# openVTI-Shield-RevC.net
KiCad netlist of a schematic drawn in EAGLE
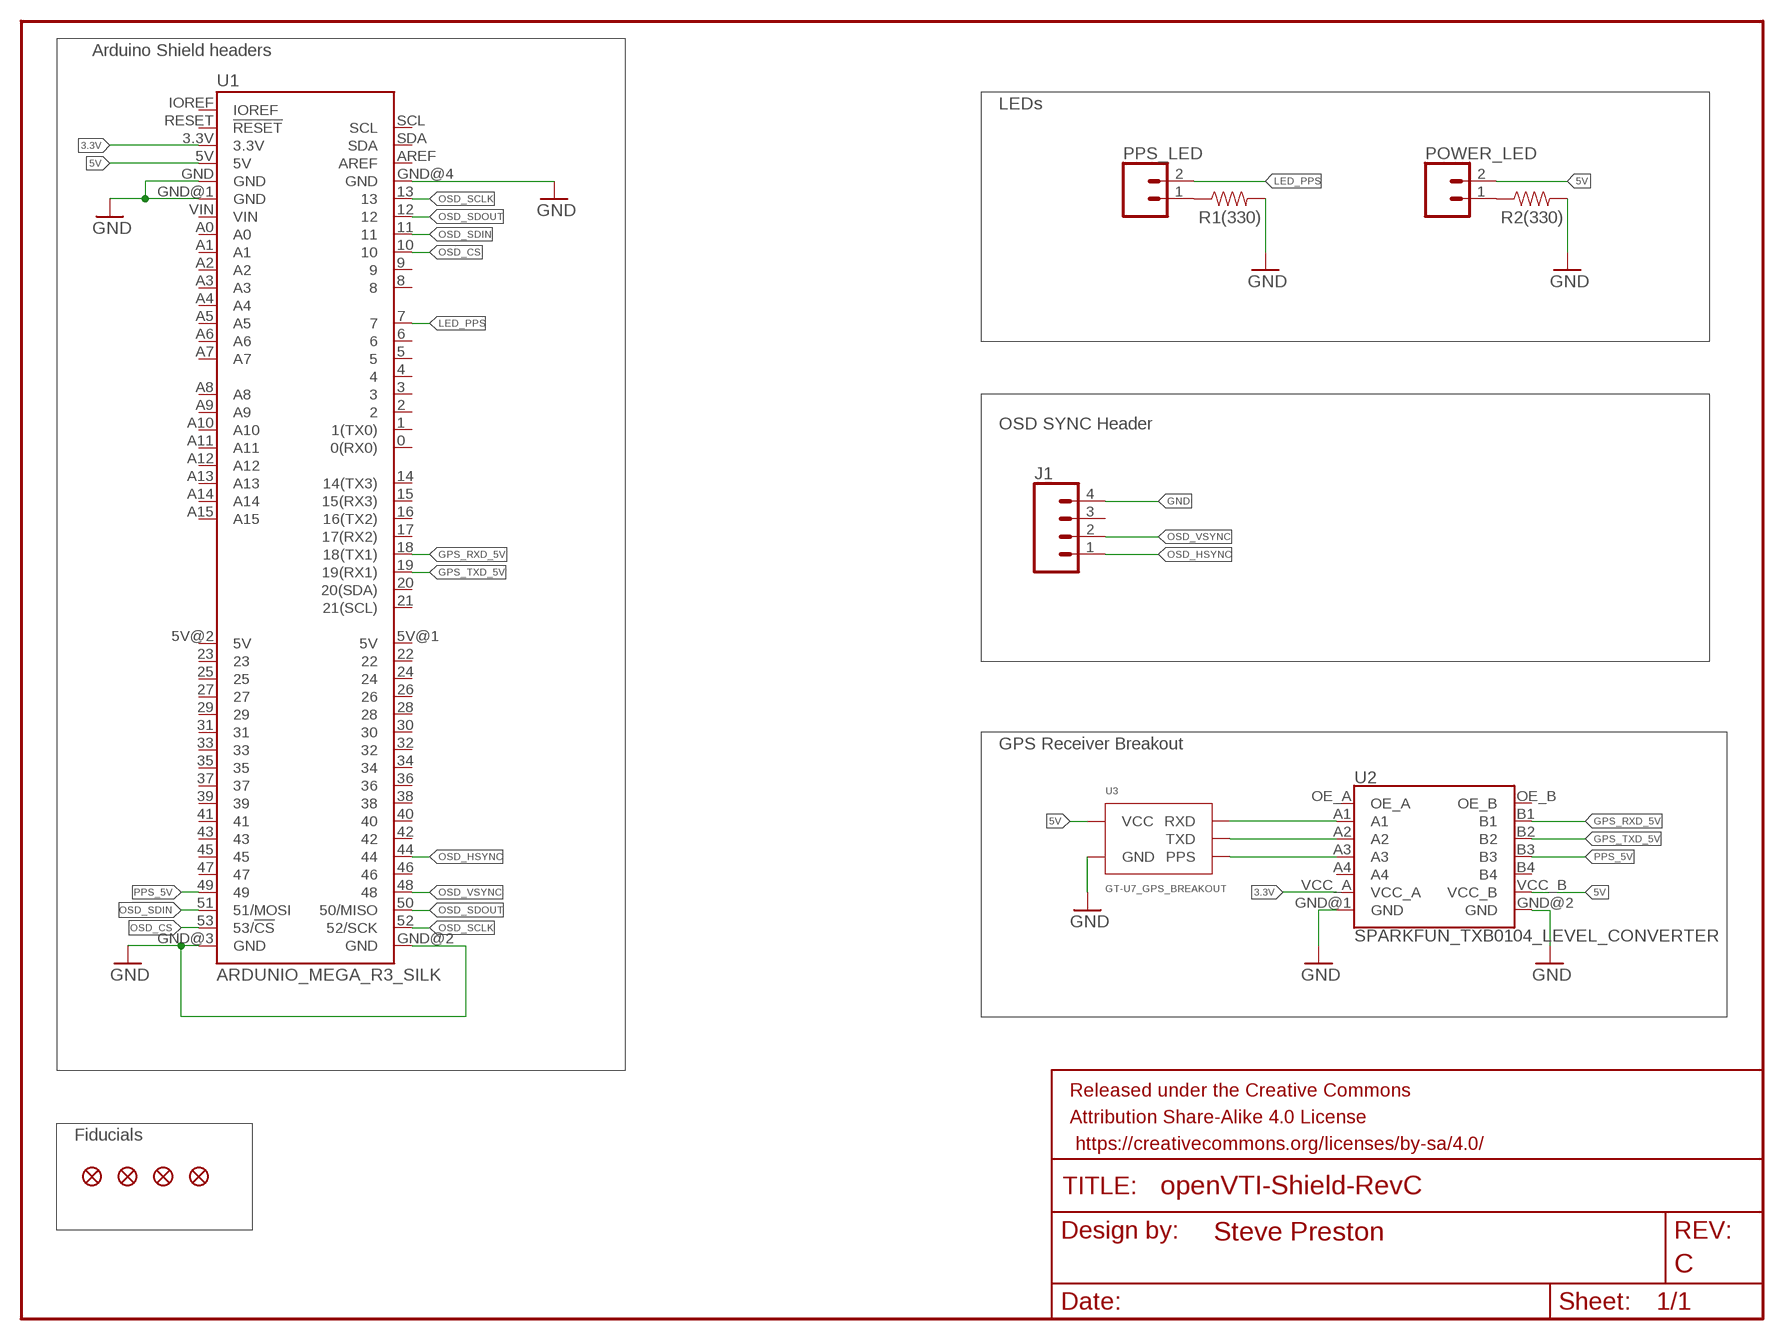
[diagram p0: schematic, sheet 1]

(export (version "E")
  (design (tool "Eeschema 10.0.6"))
  (components
    (comp (ref "FD1")
      (value "FIDUCIALUFIDUCIAL")
      (footprint "eagle-import:FIDUCIAL-MICRO")
      (libsource (lib "eagle-import") (part "FIDUCIALUFIDUCIAL"))
    )
    (comp (ref "FD2")
      (value "FIDUCIALUFIDUCIAL")
      (footprint "eagle-import:FIDUCIAL-MICRO")
      (libsource (lib "eagle-import") (part "FIDUCIALUFIDUCIAL"))
    )
    (comp (ref "FD3")
      (value "FIDUCIALUFIDUCIAL")
      (footprint "eagle-import:FIDUCIAL-MICRO")
      (libsource (lib "eagle-import") (part "FIDUCIALUFIDUCIAL"))
    )
    (comp (ref "FD4")
      (value "FIDUCIALUFIDUCIAL")
      (footprint "eagle-import:FIDUCIAL-MICRO")
      (libsource (lib "eagle-import") (part "FIDUCIALUFIDUCIAL"))
    )
    (comp (ref "FRAME1")
      (value "FRAME-LETTER")
      (footprint "eagle-import:CREATIVE_COMMONS")
      (fields (field (name "DESIGNER") "Steve Preston") (field (name "REV") "C"))
      (libsource (lib "eagle-import") (part "FRAME-LETTER"))
    )
    (comp (ref "J1")
      (value "CONN_04PTH")
      (footprint "eagle-import:1X04")
      (libsource (lib "eagle-import") (part "CONN_04PTH"))
    )
    (comp (ref "POWER_LED")
      (value "CONN_02")
      (footprint "eagle-import:1X02")
      (libsource (lib "eagle-import") (part "CONN_02"))
    )
    (comp (ref "PPS_LED")
      (value "CONN_02")
      (footprint "eagle-import:1X02")
      (libsource (lib "eagle-import") (part "CONN_02"))
    )
    (comp (ref "R1(330)")
      (value "RESISTORAXIAL-0.3")
      (footprint "eagle-import:AXIAL-0.3")
      (libsource (lib "eagle-import") (part "RESISTORAXIAL-0.3"))
    )
    (comp (ref "R2(330)")
      (value "RESISTORAXIAL-0.3")
      (footprint "eagle-import:AXIAL-0.3")
      (libsource (lib "eagle-import") (part "RESISTORAXIAL-0.3"))
    )
    (comp (ref "U1")
      (value "ARDUNIO_MEGA_R3_SILK")
      (footprint "eagle-import:ARDUINO_MEGA_SILK")
      (libsource (lib "eagle-import") (part "ARDUNIO_MEGA_R3_SILK"))
    )
    (comp (ref "U2")
      (value "SPARKFUN_TXB0104_LEVEL_CONVERTER")
      (footprint "eagle-import:TXB0104_LEVEL_CONVERTER")
      (libsource (lib "eagle-import") (part "SPARKFUN_TXB0104_LEVEL_CONVERTER"))
    )
    (comp (ref "U3")
      (value "GT-U7_GPS_BREAKOUT")
      (footprint "eagle-import:GT-UT")
      (libsource (lib "eagle-import") (part "GT-U7_GPS_BREAKOUT"))
    )
  )
  (nets
    (net (code "1") (name "3.3V") (class "Default")
      (node (ref "U1") (pin "3.3V") (pinfunction "3.3V_3.3V") (pintype "bidirectional"))
      (node (ref "U2") (pin "VCC_A") (pinfunction "VCC_A_VCC_A") (pintype "power_in"))
    )
    (net (code "2") (name "5V") (class "Default")
      (node (ref "POWER_LED") (pin "2") (pinfunction "2_2") (pintype "passive"))
      (node (ref "U1") (pin "5V") (pinfunction "5V_5V") (pintype "bidirectional"))
      (node (ref "U2") (pin "VCC_B") (pinfunction "VCC_B_VCC_B") (pintype "power_in"))
      (node (ref "U3") (pin "VCC") (pinfunction "VCC_VCC") (pintype "power_in"))
    )
    (net (code "3") (name "GND") (class "Default")
      (node (ref "J1") (pin "4") (pinfunction "4_4") (pintype "passive"))
      (node (ref "R1(330)") (pin "P$2") (pinfunction "2_P$2") (pintype "passive"))
      (node (ref "R2(330)") (pin "P$2") (pinfunction "2_P$2") (pintype "passive"))
      (node (ref "U1") (pin "GND") (pinfunction "GND_GND") (pintype "bidirectional"))
      (node (ref "U1") (pin "GND@1") (pinfunction "GND_GND@1") (pintype "bidirectional"))
      (node (ref "U1") (pin "GND@2") (pinfunction "GND_GND@2") (pintype "bidirectional"))
      (node (ref "U1") (pin "GND@3") (pinfunction "GND_GND@3") (pintype "bidirectional"))
      (node (ref "U1") (pin "GND@4") (pinfunction "GND_GND@4") (pintype "bidirectional"))
      (node (ref "U2") (pin "GND@1") (pinfunction "GND_GND@1") (pintype "power_in"))
      (node (ref "U2") (pin "GND@2") (pinfunction "GND_GND@2") (pintype "power_in"))
      (node (ref "U3") (pin "GND") (pinfunction "GND_GND") (pintype "power_in"))
    )
    (net (code "4") (name "GPS_RXD_5V") (class "Default")
      (node (ref "U1") (pin "18") (pinfunction "18(TX1)_18") (pintype "bidirectional"))
      (node (ref "U2") (pin "B1") (pinfunction "B1_B1") (pintype "bidirectional"))
    )
    (net (code "5") (name "GPS_TXD_5V") (class "Default")
      (node (ref "U1") (pin "19") (pinfunction "19(RX1)_19") (pintype "bidirectional"))
      (node (ref "U2") (pin "B2") (pinfunction "B2_B2") (pintype "bidirectional"))
    )
    (net (code "6") (name "LED_PPS") (class "Default")
      (node (ref "PPS_LED") (pin "2") (pinfunction "2_2") (pintype "passive"))
      (node (ref "U1") (pin "7") (pinfunction "7_7") (pintype "bidirectional"))
    )
    (net (code "7") (name "Net-(R1(330)-1)") (class "Default")
      (node (ref "PPS_LED") (pin "1") (pinfunction "1_1") (pintype "passive"))
      (node (ref "R1(330)") (pin "P$1") (pinfunction "1_P$1") (pintype "passive"))
    )
    (net (code "8") (name "Net-(R2(330)-1)") (class "Default")
      (node (ref "POWER_LED") (pin "1") (pinfunction "1_1") (pintype "passive"))
      (node (ref "R2(330)") (pin "P$1") (pinfunction "1_P$1") (pintype "passive"))
    )
    (net (code "9") (name "Net-(U2-PadA1)") (class "Default")
      (node (ref "U2") (pin "A1") (pinfunction "A1_A1") (pintype "bidirectional"))
      (node (ref "U3") (pin "RXD") (pinfunction "RXD_RXD") (pintype "bidirectional"))
    )
    (net (code "10") (name "Net-(U2-PadA2)") (class "Default")
      (node (ref "U2") (pin "A2") (pinfunction "A2_A2") (pintype "bidirectional"))
      (node (ref "U3") (pin "TXD") (pinfunction "TXD_TXD") (pintype "bidirectional"))
    )
    (net (code "11") (name "Net-(U2-PadA3)") (class "Default")
      (node (ref "U2") (pin "A3") (pinfunction "A3_A3") (pintype "bidirectional"))
      (node (ref "U3") (pin "PPS") (pinfunction "PPS_PPS") (pintype "bidirectional"))
    )
    (net (code "12") (name "OSD_CS") (class "Default")
      (node (ref "U1") (pin "10") (pinfunction "10_10") (pintype "bidirectional"))
      (node (ref "U1") (pin "53") (pinfunction "53/~{CS}_53") (pintype "bidirectional"))
    )
    (net (code "13") (name "OSD_HSYNC") (class "Default")
      (node (ref "J1") (pin "1") (pinfunction "1_1") (pintype "passive"))
      (node (ref "U1") (pin "44") (pinfunction "44_44") (pintype "bidirectional"))
    )
    (net (code "14") (name "OSD_SCLK") (class "Default")
      (node (ref "U1") (pin "13") (pinfunction "13_13") (pintype "bidirectional"))
      (node (ref "U1") (pin "52") (pinfunction "52/SCK_52") (pintype "bidirectional"))
    )
    (net (code "15") (name "OSD_SDIN") (class "Default")
      (node (ref "U1") (pin "11") (pinfunction "11_11") (pintype "bidirectional"))
      (node (ref "U1") (pin "51") (pinfunction "51/MOSI_51") (pintype "bidirectional"))
    )
    (net (code "16") (name "OSD_SDOUT") (class "Default")
      (node (ref "U1") (pin "12") (pinfunction "12_12") (pintype "bidirectional"))
      (node (ref "U1") (pin "50") (pinfunction "50/MISO_50") (pintype "bidirectional"))
    )
    (net (code "17") (name "OSD_VSYNC") (class "Default")
      (node (ref "J1") (pin "2") (pinfunction "2_2") (pintype "passive"))
      (node (ref "U1") (pin "48") (pinfunction "48_48") (pintype "bidirectional"))
    )
    (net (code "18") (name "PPS_5V") (class "Default")
      (node (ref "U1") (pin "49") (pinfunction "49_49") (pintype "bidirectional"))
      (node (ref "U2") (pin "B3") (pinfunction "B3_B3") (pintype "bidirectional"))
    )
    (net (code "19") (name "unconnected-(J1-Pad3)") (class "Default")
      (node (ref "J1") (pin "3") (pinfunction "3_3") (pintype "passive"))
    )
    (net (code "20") (name "unconnected-(U1-0(RX0)-Pad0)") (class "Default")
      (node (ref "U1") (pin "0") (pinfunction "0(RX0)_0") (pintype "bidirectional"))
    )
    (net (code "21") (name "unconnected-(U1-1(TX0)-Pad1)") (class "Default")
      (node (ref "U1") (pin "1") (pinfunction "1(TX0)_1") (pintype "bidirectional"))
    )
    (net (code "22") (name "unconnected-(U1-5V-Pad5V@1)") (class "Default")
      (node (ref "U1") (pin "5V@1") (pinfunction "5V_5V@1") (pintype "bidirectional"))
    )
    (net (code "23") (name "unconnected-(U1-5V-Pad5V@2)") (class "Default")
      (node (ref "U1") (pin "5V@2") (pinfunction "5V_5V@2") (pintype "bidirectional"))
    )
    (net (code "24") (name "unconnected-(U1-14(TX3)-Pad14)") (class "Default")
      (node (ref "U1") (pin "14") (pinfunction "14(TX3)_14") (pintype "bidirectional"))
    )
    (net (code "25") (name "unconnected-(U1-15(RX3)-Pad15)") (class "Default")
      (node (ref "U1") (pin "15") (pinfunction "15(RX3)_15") (pintype "bidirectional"))
    )
    (net (code "26") (name "unconnected-(U1-16(TX2)-Pad16)") (class "Default")
      (node (ref "U1") (pin "16") (pinfunction "16(TX2)_16") (pintype "bidirectional"))
    )
    (net (code "27") (name "unconnected-(U1-17(RX2)-Pad17)") (class "Default")
      (node (ref "U1") (pin "17") (pinfunction "17(RX2)_17") (pintype "bidirectional"))
    )
    (net (code "28") (name "unconnected-(U1-20(SDA)-Pad20)") (class "Default")
      (node (ref "U1") (pin "20") (pinfunction "20(SDA)_20") (pintype "bidirectional"))
    )
    (net (code "29") (name "unconnected-(U1-21(SCL)-Pad21)") (class "Default")
      (node (ref "U1") (pin "21") (pinfunction "21(SCL)_21") (pintype "bidirectional"))
    )
    (net (code "30") (name "unconnected-(U1-Pad2)") (class "Default")
      (node (ref "U1") (pin "2") (pinfunction "2_2") (pintype "bidirectional"))
    )
    (net (code "31") (name "unconnected-(U1-Pad3)") (class "Default")
      (node (ref "U1") (pin "3") (pinfunction "3_3") (pintype "bidirectional"))
    )
    (net (code "32") (name "unconnected-(U1-Pad4)") (class "Default")
      (node (ref "U1") (pin "4") (pinfunction "4_4") (pintype "bidirectional"))
    )
    (net (code "33") (name "unconnected-(U1-Pad5)") (class "Default")
      (node (ref "U1") (pin "5") (pinfunction "5_5") (pintype "bidirectional"))
    )
    (net (code "34") (name "unconnected-(U1-Pad6)") (class "Default")
      (node (ref "U1") (pin "6") (pinfunction "6_6") (pintype "bidirectional"))
    )
    (net (code "35") (name "unconnected-(U1-Pad8)") (class "Default")
      (node (ref "U1") (pin "8") (pinfunction "8_8") (pintype "bidirectional"))
    )
    (net (code "36") (name "unconnected-(U1-Pad9)") (class "Default")
      (node (ref "U1") (pin "9") (pinfunction "9_9") (pintype "bidirectional"))
    )
    (net (code "37") (name "unconnected-(U1-Pad22)") (class "Default")
      (node (ref "U1") (pin "22") (pinfunction "22_22") (pintype "bidirectional"))
    )
    (net (code "38") (name "unconnected-(U1-Pad23)") (class "Default")
      (node (ref "U1") (pin "23") (pinfunction "23_23") (pintype "bidirectional"))
    )
    (net (code "39") (name "unconnected-(U1-Pad24)") (class "Default")
      (node (ref "U1") (pin "24") (pinfunction "24_24") (pintype "bidirectional"))
    )
    (net (code "40") (name "unconnected-(U1-Pad25)") (class "Default")
      (node (ref "U1") (pin "25") (pinfunction "25_25") (pintype "bidirectional"))
    )
    (net (code "41") (name "unconnected-(U1-Pad26)") (class "Default")
      (node (ref "U1") (pin "26") (pinfunction "26_26") (pintype "bidirectional"))
    )
    (net (code "42") (name "unconnected-(U1-Pad27)") (class "Default")
      (node (ref "U1") (pin "27") (pinfunction "27_27") (pintype "bidirectional"))
    )
    (net (code "43") (name "unconnected-(U1-Pad28)") (class "Default")
      (node (ref "U1") (pin "28") (pinfunction "28_28") (pintype "bidirectional"))
    )
    (net (code "44") (name "unconnected-(U1-Pad29)") (class "Default")
      (node (ref "U1") (pin "29") (pinfunction "29_29") (pintype "bidirectional"))
    )
    (net (code "45") (name "unconnected-(U1-Pad30)") (class "Default")
      (node (ref "U1") (pin "30") (pinfunction "30_30") (pintype "bidirectional"))
    )
    (net (code "46") (name "unconnected-(U1-Pad31)") (class "Default")
      (node (ref "U1") (pin "31") (pinfunction "31_31") (pintype "bidirectional"))
    )
    (net (code "47") (name "unconnected-(U1-Pad32)") (class "Default")
      (node (ref "U1") (pin "32") (pinfunction "32_32") (pintype "bidirectional"))
    )
    (net (code "48") (name "unconnected-(U1-Pad33)") (class "Default")
      (node (ref "U1") (pin "33") (pinfunction "33_33") (pintype "bidirectional"))
    )
    (net (code "49") (name "unconnected-(U1-Pad34)") (class "Default")
      (node (ref "U1") (pin "34") (pinfunction "34_34") (pintype "bidirectional"))
    )
    (net (code "50") (name "unconnected-(U1-Pad35)") (class "Default")
      (node (ref "U1") (pin "35") (pinfunction "35_35") (pintype "bidirectional"))
    )
    (net (code "51") (name "unconnected-(U1-Pad36)") (class "Default")
      (node (ref "U1") (pin "36") (pinfunction "36_36") (pintype "bidirectional"))
    )
    (net (code "52") (name "unconnected-(U1-Pad37)") (class "Default")
      (node (ref "U1") (pin "37") (pinfunction "37_37") (pintype "bidirectional"))
    )
    (net (code "53") (name "unconnected-(U1-Pad38)") (class "Default")
      (node (ref "U1") (pin "38") (pinfunction "38_38") (pintype "bidirectional"))
    )
    (net (code "54") (name "unconnected-(U1-Pad39)") (class "Default")
      (node (ref "U1") (pin "39") (pinfunction "39_39") (pintype "bidirectional"))
    )
    (net (code "55") (name "unconnected-(U1-Pad40)") (class "Default")
      (node (ref "U1") (pin "40") (pinfunction "40_40") (pintype "bidirectional"))
    )
    (net (code "56") (name "unconnected-(U1-Pad41)") (class "Default")
      (node (ref "U1") (pin "41") (pinfunction "41_41") (pintype "bidirectional"))
    )
    (net (code "57") (name "unconnected-(U1-Pad42)") (class "Default")
      (node (ref "U1") (pin "42") (pinfunction "42_42") (pintype "bidirectional"))
    )
    (net (code "58") (name "unconnected-(U1-Pad43)") (class "Default")
      (node (ref "U1") (pin "43") (pinfunction "43_43") (pintype "bidirectional"))
    )
    (net (code "59") (name "unconnected-(U1-Pad45)") (class "Default")
      (node (ref "U1") (pin "45") (pinfunction "45_45") (pintype "bidirectional"))
    )
    (net (code "60") (name "unconnected-(U1-Pad46)") (class "Default")
      (node (ref "U1") (pin "46") (pinfunction "46_46") (pintype "bidirectional"))
    )
    (net (code "61") (name "unconnected-(U1-Pad47)") (class "Default")
      (node (ref "U1") (pin "47") (pinfunction "47_47") (pintype "bidirectional"))
    )
    (net (code "62") (name "unconnected-(U1-PadA0)") (class "Default")
      (node (ref "U1") (pin "A0") (pinfunction "A0_A0") (pintype "bidirectional"))
    )
    (net (code "63") (name "unconnected-(U1-PadA1)") (class "Default")
      (node (ref "U1") (pin "A1") (pinfunction "A1_A1") (pintype "bidirectional"))
    )
    (net (code "64") (name "unconnected-(U1-PadA2)") (class "Default")
      (node (ref "U1") (pin "A2") (pinfunction "A2_A2") (pintype "bidirectional"))
    )
    (net (code "65") (name "unconnected-(U1-PadA3)") (class "Default")
      (node (ref "U1") (pin "A3") (pinfunction "A3_A3") (pintype "bidirectional"))
    )
    (net (code "66") (name "unconnected-(U1-PadA4)") (class "Default")
      (node (ref "U1") (pin "A4") (pinfunction "A4_A4") (pintype "bidirectional"))
    )
    (net (code "67") (name "unconnected-(U1-PadA5)") (class "Default")
      (node (ref "U1") (pin "A5") (pinfunction "A5_A5") (pintype "bidirectional"))
    )
    (net (code "68") (name "unconnected-(U1-PadA6)") (class "Default")
      (node (ref "U1") (pin "A6") (pinfunction "A6_A6") (pintype "bidirectional"))
    )
    (net (code "69") (name "unconnected-(U1-PadA7)") (class "Default")
      (node (ref "U1") (pin "A7") (pinfunction "A7_A7") (pintype "bidirectional"))
    )
    (net (code "70") (name "unconnected-(U1-PadA8)") (class "Default")
      (node (ref "U1") (pin "A8") (pinfunction "A8_A8") (pintype "bidirectional"))
    )
    (net (code "71") (name "unconnected-(U1-PadA9)") (class "Default")
      (node (ref "U1") (pin "A9") (pinfunction "A9_A9") (pintype "bidirectional"))
    )
    (net (code "72") (name "unconnected-(U1-PadA10)") (class "Default")
      (node (ref "U1") (pin "A10") (pinfunction "A10_A10") (pintype "bidirectional"))
    )
    (net (code "73") (name "unconnected-(U1-PadA11)") (class "Default")
      (node (ref "U1") (pin "A11") (pinfunction "A11_A11") (pintype "bidirectional"))
    )
    (net (code "74") (name "unconnected-(U1-PadA12)") (class "Default")
      (node (ref "U1") (pin "A12") (pinfunction "A12_A12") (pintype "bidirectional"))
    )
    (net (code "75") (name "unconnected-(U1-PadA13)") (class "Default")
      (node (ref "U1") (pin "A13") (pinfunction "A13_A13") (pintype "bidirectional"))
    )
    (net (code "76") (name "unconnected-(U1-PadA14)") (class "Default")
      (node (ref "U1") (pin "A14") (pinfunction "A14_A14") (pintype "bidirectional"))
    )
    (net (code "77") (name "unconnected-(U1-PadA15)") (class "Default")
      (node (ref "U1") (pin "A15") (pinfunction "A15_A15") (pintype "bidirectional"))
    )
    (net (code "78") (name "unconnected-(U1-PadAREF)") (class "Default")
      (node (ref "U1") (pin "AREF") (pinfunction "AREF_AREF") (pintype "bidirectional"))
    )
    (net (code "79") (name "unconnected-(U1-PadIOREF)") (class "Default")
      (node (ref "U1") (pin "IOREF") (pinfunction "IOREF_IOREF") (pintype "bidirectional"))
    )
    (net (code "80") (name "unconnected-(U1-PadSCL)") (class "Default")
      (node (ref "U1") (pin "SCL") (pinfunction "SCL_SCL") (pintype "bidirectional"))
    )
    (net (code "81") (name "unconnected-(U1-PadSDA)") (class "Default")
      (node (ref "U1") (pin "SDA") (pinfunction "SDA_SDA") (pintype "bidirectional"))
    )
    (net (code "82") (name "unconnected-(U1-PadVIN)") (class "Default")
      (node (ref "U1") (pin "VIN") (pinfunction "VIN_VIN") (pintype "bidirectional"))
    )
    (net (code "83") (name "unconnected-(U1-~{RESET}-PadRESET)") (class "Default")
      (node (ref "U1") (pin "RESET") (pinfunction "~{RESET}_RESET") (pintype "bidirectional"))
    )
    (net (code "84") (name "unconnected-(U2-PadA4)") (class "Default")
      (node (ref "U2") (pin "A4") (pinfunction "A4_A4") (pintype "bidirectional"))
    )
    (net (code "85") (name "unconnected-(U2-PadB4)") (class "Default")
      (node (ref "U2") (pin "B4") (pinfunction "B4_B4") (pintype "bidirectional"))
    )
    (net (code "86") (name "unconnected-(U2-PadOE_A)") (class "Default")
      (node (ref "U2") (pin "OE_A") (pinfunction "OE_A_OE_A") (pintype "bidirectional"))
    )
    (net (code "87") (name "unconnected-(U2-PadOE_B)") (class "Default")
      (node (ref "U2") (pin "OE_B") (pinfunction "OE_B_OE_B") (pintype "bidirectional"))
    )
  )
)
